# GPSDO_Controller.net
KiCad netlist of a schematic drawn in Altium Designer
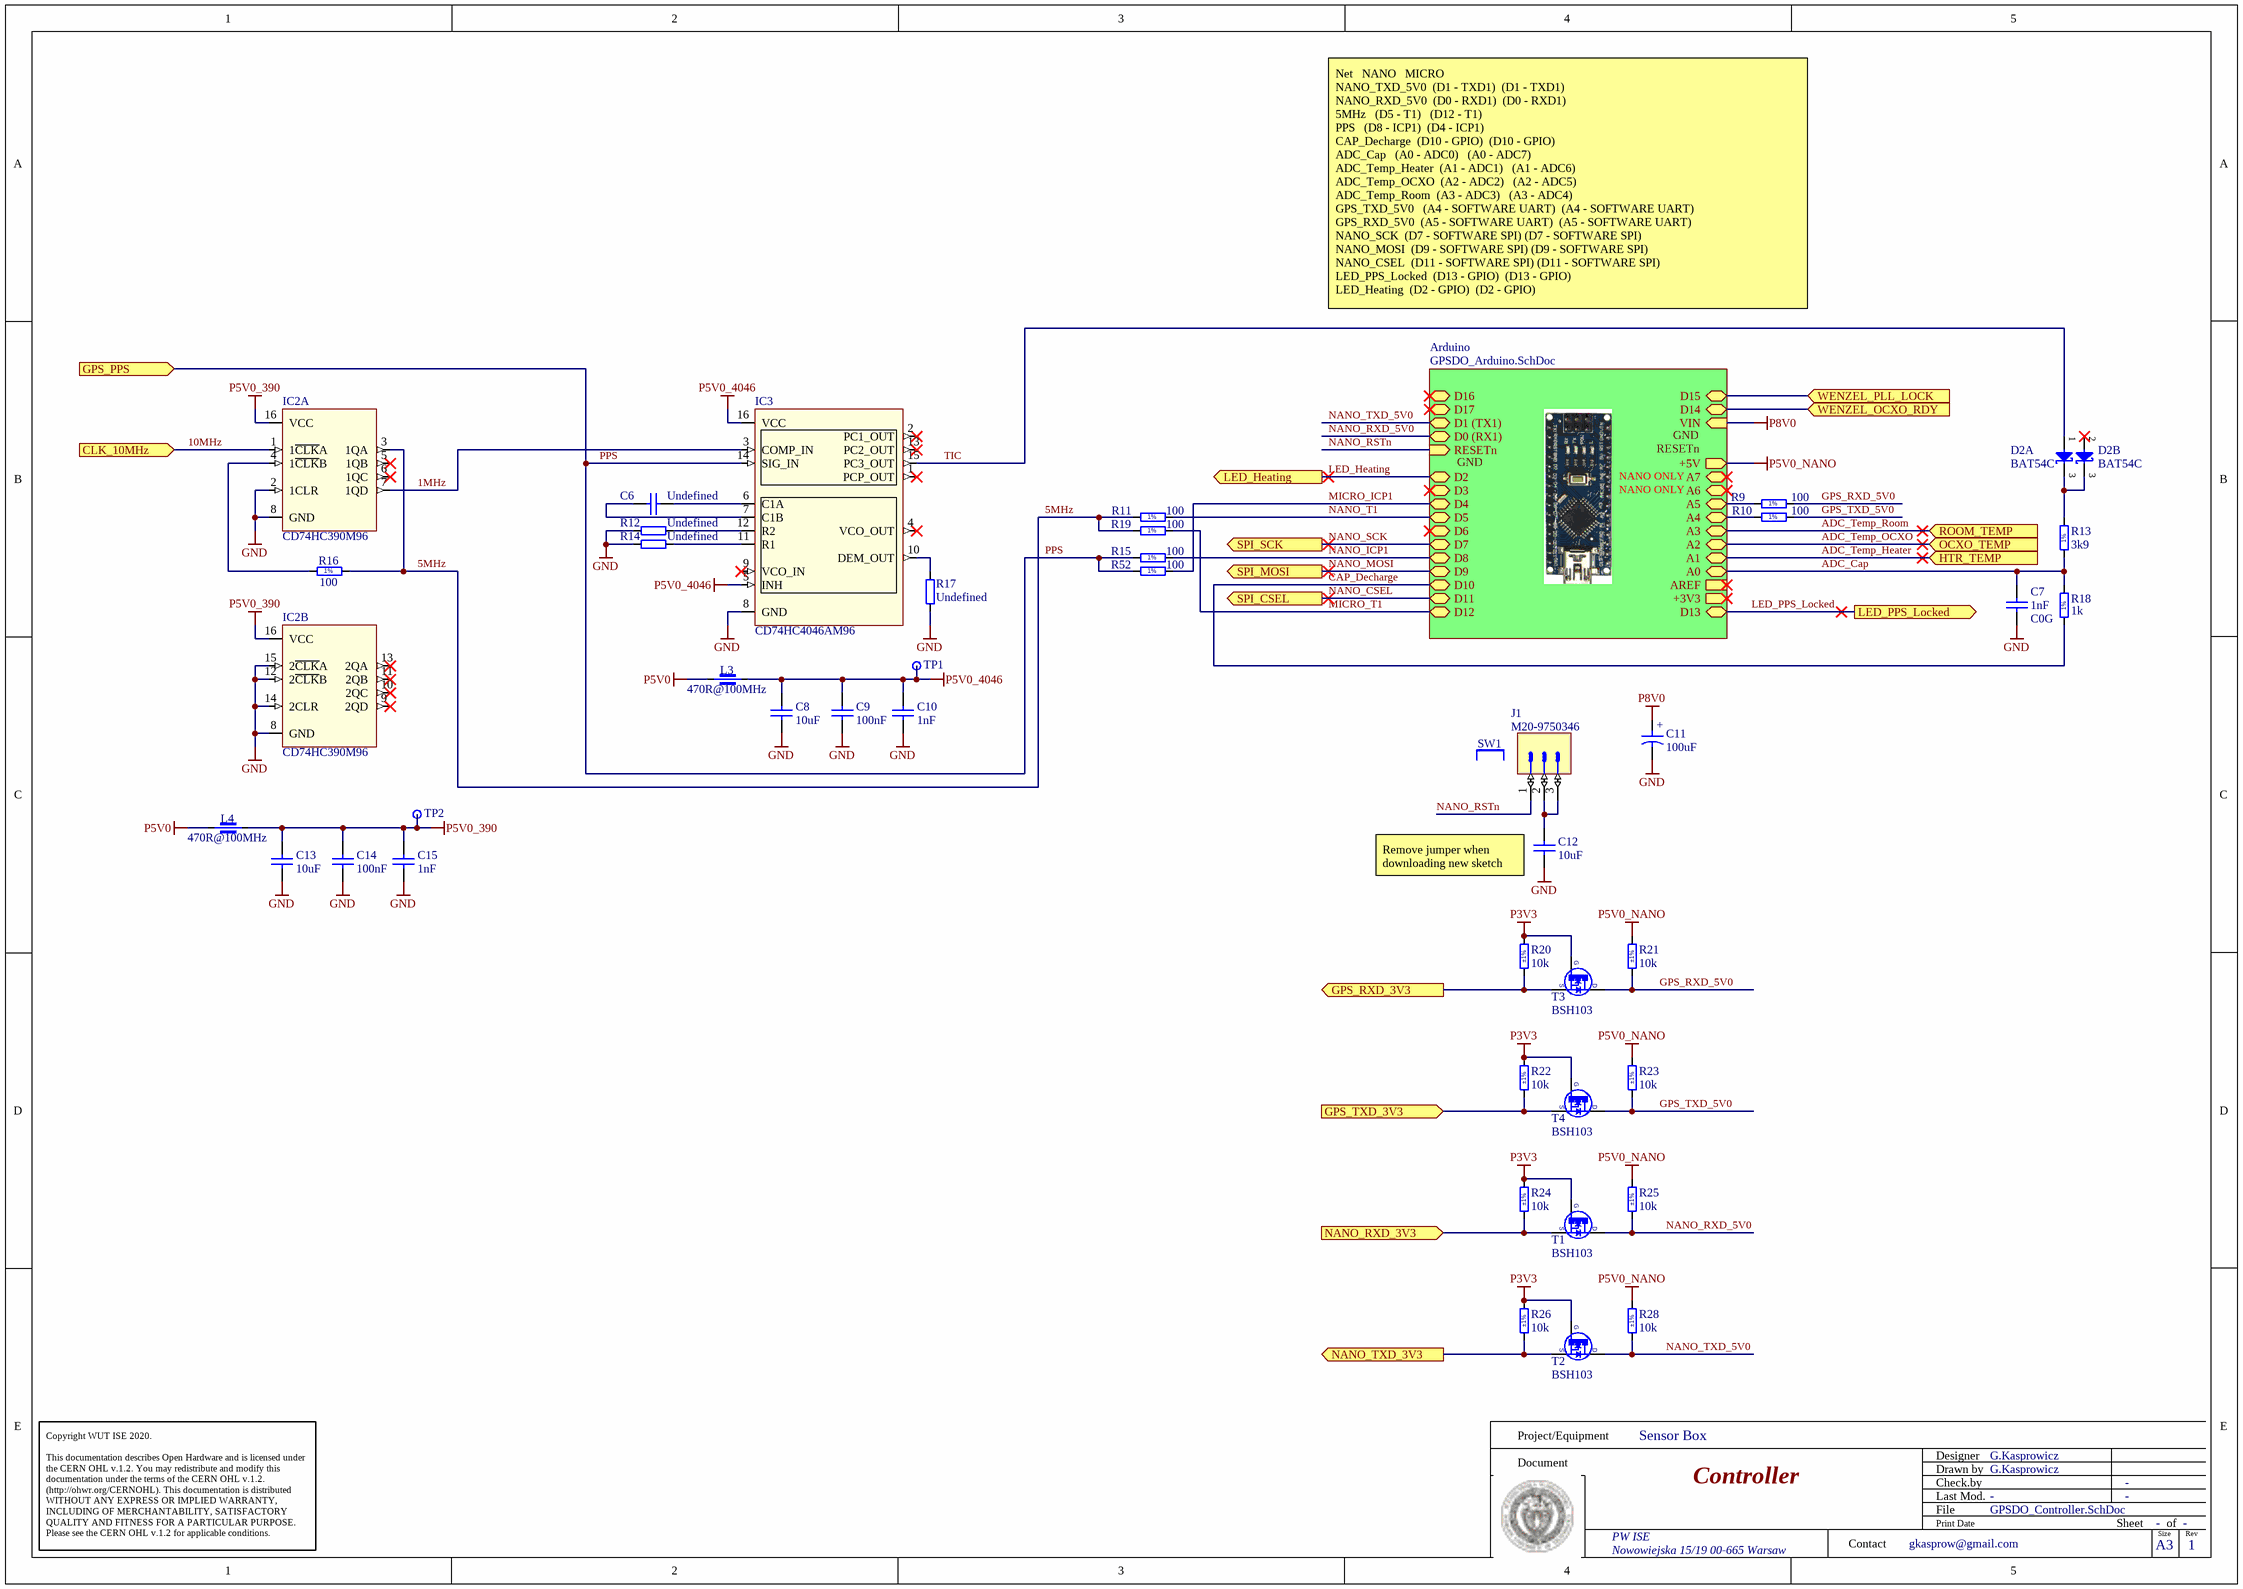
[diagram p0: GPSDO_Controller.SchDoc]

(export (version "E")
  (design (tool "Eeschema 10.0.6"))
  (components
    (comp (ref "C6")
      (value "Undefined")
      (footprint "CAPC1005X55N")
      (description "Non-polarised capacitor")
      (fields (field (name "PART NUMBER") "CC0402_NO-VALUE") (field (name "AUTHOR") "CERN DEM JLC"))
      (libsource (lib "Capacitors") (part "Capacitor - non polarized"))
    )
    (comp (ref "C7")
      (value "1nF")
      (footprint "CAPC1608X90N")
      (description "Non-polarised capacitor")
      (fields
        (field (name "PART NUMBER") "CC0603_1NF_50V_1%_NP0")
        (field (name "VOLTAGE") "50V")
        (field (name "TC") "C0G")
        (field (name "AUTHOR") "CERN DEM JLC")
      )
      (libsource (lib "Capacitors") (part "Capacitor - non polarized"))
    )
    (comp (ref "C8")
      (value "10uF")
      (footprint "CAPC1608X80N")
      (description "Non-polarised capacitor")
      (fields
        (field (name "PART NUMBER") "CC0603_10UF_10V_10%_X5R")
        (field (name "VOLTAGE") "10V")
        (field (name "AUTHOR") "CERN DEM JLC")
      )
      (libsource (lib "Capacitors") (part "Capacitor - non polarized"))
    )
    (comp (ref "C9")
      (value "100nF")
      (footprint "CAPC1005X55N")
      (description "Non-polarised capacitor")
      (fields
        (field (name "PART NUMBER") "CC0402_100NF_16V_10%_X5R")
        (field (name "VOLTAGE") "16V")
        (field (name "AUTHOR") "CERN DEM JLC")
      )
      (libsource (lib "Capacitors") (part "Capacitor - non polarized"))
    )
    (comp (ref "C10")
      (value "1nF")
      (footprint "CAPC1608X90N")
      (description "Non-polarised capacitor")
      (fields
        (field (name "PART NUMBER") "CC0603_1NF_50V_1%_NP0")
        (field (name "VOLTAGE") "50V")
        (field (name "AUTHOR") "CERN DEM JLC")
      )
      (libsource (lib "Capacitors") (part "Capacitor - non polarized"))
    )
    (comp (ref "C11")
      (value "100uF")
      (footprint "CAPMP7343X310N")
      (description "Polarised capacitor")
      (fields
        (field (name "PART NUMBER") "CTE7343-31_100UF_20V_10%")
        (field (name "VOLTAGE") "20V")
        (field (name "AUTHOR") "CERN DEM JLC")
      )
      (libsource (lib "Capacitors") (part "Capacitor - polarized"))
    )
    (comp (ref "C12")
      (value "10uF")
      (footprint "CAPC1608X80N")
      (description "Non-polarised capacitor")
      (fields
        (field (name "PART NUMBER") "CC0603_10UF_10V_10%_X5R")
        (field (name "VOLTAGE") "10V")
        (field (name "AUTHOR") "CERN DEM JLC")
      )
      (libsource (lib "Capacitors") (part "Capacitor - non polarized"))
    )
    (comp (ref "C13")
      (value "10uF")
      (footprint "CAPC1608X80N")
      (description "Non-polarised capacitor")
      (fields
        (field (name "PART NUMBER") "CC0603_10UF_10V_10%_X5R")
        (field (name "VOLTAGE") "10V")
        (field (name "AUTHOR") "CERN DEM JLC")
      )
      (libsource (lib "Capacitors") (part "Capacitor - non polarized"))
    )
    (comp (ref "C14")
      (value "100nF")
      (footprint "CAPC1005X55N")
      (description "Non-polarised capacitor")
      (fields
        (field (name "PART NUMBER") "CC0402_100NF_16V_10%_X5R")
        (field (name "VOLTAGE") "16V")
        (field (name "AUTHOR") "CERN DEM JLC")
      )
      (libsource (lib "Capacitors") (part "Capacitor - non polarized"))
    )
    (comp (ref "C15")
      (value "1nF")
      (footprint "CAPC1608X90N")
      (description "Non-polarised capacitor")
      (fields
        (field (name "PART NUMBER") "CC0603_1NF_50V_1%_NP0")
        (field (name "VOLTAGE") "50V")
        (field (name "AUTHOR") "CERN DEM JLC")
      )
      (libsource (lib "Capacitors") (part "Capacitor - non polarized"))
    )
    (comp (ref "D2")
      (value "BAT54C")
      (footprint "SOT95P240X130-3N")
      (description "Dual Common Cathode Schottky Diodes")
      (fields
        (field (name "VOLTAGE") "30V")
        (field (name "POWER") "200mA")
        (field (name "AUTHOR") "CERN DEM JLC")
      )
      (libsource (lib "ICs And Semiconductors") (part "Diode Schottky x2 A1C3_A2C3"))
    )
    (comp (ref "IC2")
      (value "CD74HC390M96")
      (footprint "SOIC127P600X175-16N")
      (libsource (lib "Lib") (part "74HC390"))
    )
    (comp (ref "IC3")
      (value "CD74HC4046AM96")
      (footprint "SOIC127P600X175-16N")
      (libsource (lib "Lib") (part "74HC4046A"))
    )
    (comp (ref "J1")
      (value "M20-9750346")
      (footprint "HARWIN_M20-9750346")
      (description "Connector 3 Male 2.54mm")
      (fields (field (name "MANUFACTURER") "Harwin"))
      (libsource (lib "Connectors") (part "Connector 3 Male_1"))
    )
    (comp (ref "L3")
      (value "470R@100MHz")
      (footprint "INDC1608X95N")
      (fields
        (field (name "PART NUMBER") "IND0603_MURATA_BLM18PG471SN1D")
        (field (name "POWER") "1A")
        (field (name "TOLERANCE") "±25%")
        (field (name "AUTHOR") "CERN DEM BC")
      )
      (libsource (lib "Inductors & Transformers") (part "Ferrite Bead"))
    )
    (comp (ref "L4")
      (value "470R@100MHz")
      (footprint "INDC1608X95N")
      (fields
        (field (name "PART NUMBER") "IND0603_MURATA_BLM18PG471SN1D")
        (field (name "POWER") "1A")
        (field (name "TOLERANCE") "±25%")
        (field (name "AUTHOR") "CERN DEM BC")
      )
      (libsource (lib "Inductors & Transformers") (part "Ferrite Bead"))
    )
    (comp (ref "R9")
      (value "100")
      (footprint "RESC1005X40N")
      (description "Resistor - 1%")
      (fields
        (field (name "PART NUMBER") "R0402_100R_1%_0.0625W_100PPM")
        (field (name "POWER") "0.0625W")
        (field (name "AUTHOR") "CERN DEM JLC")
      )
      (libsource (lib "Resistors") (part "Resistor - 1%"))
    )
    (comp (ref "R10")
      (value "100")
      (footprint "RESC1005X40N")
      (description "Resistor - 1%")
      (fields
        (field (name "PART NUMBER") "R0402_100R_1%_0.0625W_100PPM")
        (field (name "POWER") "0.0625W")
        (field (name "AUTHOR") "CERN DEM JLC")
      )
      (libsource (lib "Resistors") (part "Resistor - 1%"))
    )
    (comp (ref "R11")
      (value "100")
      (footprint "RESC1005X40N")
      (description "Resistor - 1%")
      (fields
        (field (name "PART NUMBER") "R0402_100R_1%_0.0625W_100PPM")
        (field (name "POWER") "0.0625W")
        (field (name "AUTHOR") "CERN DEM JLC")
      )
      (libsource (lib "Resistors") (part "Resistor - 1%"))
    )
    (comp (ref "R12")
      (value "Undefined")
      (footprint "RESC1005X40N")
      (description "Resistor")
      (fields (field (name "PART NUMBER") "R0402_NO-VALUE") (field (name "AUTHOR") "CERN DEM JLC"))
      (libsource (lib "Resistors") (part "Resistor"))
    )
    (comp (ref "R13")
      (value "3k9")
      (footprint "RESC1005X40N")
      (description "Resistor - 1%")
      (fields
        (field (name "PART NUMBER") "R0402_3K9_1%_0.0625W_100PPM")
        (field (name "POWER") "0.0625W")
        (field (name "AUTHOR") "CERN DEM JLC")
      )
      (libsource (lib "Resistors") (part "Resistor - 1%"))
    )
    (comp (ref "R14")
      (value "Undefined")
      (footprint "RESC1005X40N")
      (description "Resistor")
      (fields (field (name "PART NUMBER") "R0402_NO-VALUE") (field (name "AUTHOR") "CERN DEM JLC"))
      (libsource (lib "Resistors") (part "Resistor"))
    )
    (comp (ref "R15")
      (value "100")
      (footprint "RESC1005X40N")
      (description "Resistor - 1%")
      (fields
        (field (name "PART NUMBER") "R0402_100R_1%_0.0625W_100PPM")
        (field (name "POWER") "0.0625W")
        (field (name "AUTHOR") "CERN DEM JLC")
      )
      (libsource (lib "Resistors") (part "Resistor - 1%"))
    )
    (comp (ref "R16")
      (value "100")
      (footprint "RESC1005X40N")
      (description "Resistor - 1%")
      (fields
        (field (name "PART NUMBER") "R0402_100R_1%_0.0625W_100PPM")
        (field (name "POWER") "0.0625W")
        (field (name "AUTHOR") "CERN DEM JLC")
      )
      (libsource (lib "Resistors") (part "Resistor - 1%"))
    )
    (comp (ref "R17")
      (value "Undefined")
      (footprint "RESC1005X40N")
      (description "Resistor")
      (fields (field (name "PART NUMBER") "R0402_NO-VALUE") (field (name "AUTHOR") "CERN DEM JLC"))
      (libsource (lib "Resistors") (part "Resistor"))
    )
    (comp (ref "R18")
      (value "1k")
      (footprint "RESC1005X40N")
      (description "Resistor - 1%")
      (fields
        (field (name "PART NUMBER") "R0402_1K_1%_0.0625W_100PPM")
        (field (name "POWER") "0.0625W")
        (field (name "AUTHOR") "CERN DEM JLC")
      )
      (libsource (lib "Resistors") (part "Resistor - 1%"))
    )
    (comp (ref "R19")
      (value "100")
      (footprint "RESC1005X40N")
      (description "Resistor - 1%")
      (fields
        (field (name "PART NUMBER") "R0402_100R_1%_0.0625W_100PPM")
        (field (name "POWER") "0.0625W")
        (field (name "AUTHOR") "CERN DEM JLC")
      )
      (libsource (lib "Resistors") (part "Resistor - 1%"))
    )
    (comp (ref "R20")
      (value "10k")
      (footprint "RESC1005X40N")
      (description "Resistor - 1%")
      (fields
        (field (name "TOLERANCE") "±1%")
        (field (name "PART NUMBER") "R0402_10K_1%_0.0625W_100PPM")
        (field (name "POWER") "0.0625W")
        (field (name "AUTHOR") "CERN DEM JLC")
      )
      (libsource (lib "Resistors") (part "Resistor - 1%"))
    )
    (comp (ref "R21")
      (value "10k")
      (footprint "RESC1005X40N")
      (description "Resistor - 1%")
      (fields
        (field (name "TOLERANCE") "±1%")
        (field (name "PART NUMBER") "R0402_10K_1%_0.0625W_100PPM")
        (field (name "POWER") "0.0625W")
        (field (name "AUTHOR") "CERN DEM JLC")
      )
      (libsource (lib "Resistors") (part "Resistor - 1%"))
    )
    (comp (ref "R22")
      (value "10k")
      (footprint "RESC1005X40N")
      (description "Resistor - 1%")
      (fields
        (field (name "TOLERANCE") "±1%")
        (field (name "PART NUMBER") "R0402_10K_1%_0.0625W_100PPM")
        (field (name "POWER") "0.0625W")
        (field (name "AUTHOR") "CERN DEM JLC")
      )
      (libsource (lib "Resistors") (part "Resistor - 1%"))
    )
    (comp (ref "R23")
      (value "10k")
      (footprint "RESC1005X40N")
      (description "Resistor - 1%")
      (fields
        (field (name "TOLERANCE") "±1%")
        (field (name "PART NUMBER") "R0402_10K_1%_0.0625W_100PPM")
        (field (name "POWER") "0.0625W")
        (field (name "AUTHOR") "CERN DEM JLC")
      )
      (libsource (lib "Resistors") (part "Resistor - 1%"))
    )
    (comp (ref "R24")
      (value "10k")
      (footprint "RESC1005X40N")
      (description "Resistor - 1%")
      (fields
        (field (name "TOLERANCE") "±1%")
        (field (name "PART NUMBER") "R0402_10K_1%_0.0625W_100PPM")
        (field (name "POWER") "0.0625W")
        (field (name "AUTHOR") "CERN DEM JLC")
      )
      (libsource (lib "Resistors") (part "Resistor - 1%"))
    )
    (comp (ref "R25")
      (value "10k")
      (footprint "RESC1005X40N")
      (description "Resistor - 1%")
      (fields
        (field (name "TOLERANCE") "±1%")
        (field (name "PART NUMBER") "R0402_10K_1%_0.0625W_100PPM")
        (field (name "POWER") "0.0625W")
        (field (name "AUTHOR") "CERN DEM JLC")
      )
      (libsource (lib "Resistors") (part "Resistor - 1%"))
    )
    (comp (ref "R26")
      (value "10k")
      (footprint "RESC1005X40N")
      (description "Resistor - 1%")
      (fields
        (field (name "TOLERANCE") "±1%")
        (field (name "PART NUMBER") "R0402_10K_1%_0.0625W_100PPM")
        (field (name "POWER") "0.0625W")
        (field (name "AUTHOR") "CERN DEM JLC")
      )
      (libsource (lib "Resistors") (part "Resistor - 1%"))
    )
    (comp (ref "R28")
      (value "10k")
      (footprint "RESC1005X40N")
      (description "Resistor - 1%")
      (fields
        (field (name "TOLERANCE") "±1%")
        (field (name "PART NUMBER") "R0402_10K_1%_0.0625W_100PPM")
        (field (name "POWER") "0.0625W")
        (field (name "AUTHOR") "CERN DEM JLC")
      )
      (libsource (lib "Resistors") (part "Resistor - 1%"))
    )
    (comp (ref "R52")
      (value "100")
      (footprint "RESC1005X40N")
      (description "Resistor - 1%")
      (fields
        (field (name "PART NUMBER") "R0402_100R_1%_0.0625W_100PPM")
        (field (name "POWER") "0.0625W")
        (field (name "AUTHOR") "CERN DEM JLC")
      )
      (libsource (lib "Resistors") (part "Resistor - 1%"))
    )
    (comp (ref "SW1")
      (value "M7582-46")
      (footprint "HARWIN_M7582-46")
      (description "Jumper 1 Pin")
      (fields (field (name "MANUFACTURER") "Harwin"))
      (libsource (lib "Connectors") (part "HARWIN_M7582-46"))
    )
    (comp (ref "T1")
      (value "BSH103")
      (footprint "SOT95P230X110-3N")
      (description "N-CHANNEL MOSFET WITH DIODE")
      (fields (field (name "MANUFACTURER") "NEXPERIA") (field (name "AUTHOR") "CERN DEM JLC"))
      (libsource (lib "ICs And Semiconductors") (part "N-MOSFET-D 1G 2S 3D"))
    )
    (comp (ref "T2")
      (value "BSH103")
      (footprint "SOT95P230X110-3N")
      (description "N-CHANNEL MOSFET WITH DIODE")
      (fields (field (name "MANUFACTURER") "NEXPERIA") (field (name "AUTHOR") "CERN DEM JLC"))
      (libsource (lib "ICs And Semiconductors") (part "N-MOSFET-D 1G 2S 3D"))
    )
    (comp (ref "T3")
      (value "BSH103")
      (footprint "SOT95P230X110-3N")
      (description "N-CHANNEL MOSFET WITH DIODE")
      (fields (field (name "MANUFACTURER") "NEXPERIA") (field (name "AUTHOR") "CERN DEM JLC"))
      (libsource (lib "ICs And Semiconductors") (part "N-MOSFET-D 1G 2S 3D"))
    )
    (comp (ref "T4")
      (value "BSH103")
      (footprint "SOT95P230X110-3N")
      (description "N-CHANNEL MOSFET WITH DIODE")
      (fields (field (name "MANUFACTURER") "NEXPERIA") (field (name "AUTHOR") "CERN DEM JLC"))
      (libsource (lib "ICs And Semiconductors") (part "N-MOSFET-D 1G 2S 3D"))
    )
    (comp (ref "TP1")
      (value "Test Point")
      (footprint "TPS127")
      (fields (field (name "PART NUMBER") "SMD_PAD_1.27X1.27MM") (field (name "AUTHOR") "CERN DEM JLC"))
      (libsource (lib "Eletro-mechanical") (part "Test Point"))
    )
    (comp (ref "TP2")
      (value "Test Point")
      (footprint "TPS127")
      (fields (field (name "PART NUMBER") "SMD_PAD_1.27X1.27MM") (field (name "AUTHOR") "CERN DEM JLC"))
      (libsource (lib "Eletro-mechanical") (part "Test Point"))
    )
  )
  (nets
    (net (code "2") (name "/1MHz") (class "Default")
      (node (ref "IC2") (pin "7") (pinfunction "1QD_7") (pintype "output"))
      (node (ref "IC3") (pin "3") (pinfunction "COMP_IN_3") (pintype "input"))
    )
    (net (code "3") (name "/5MHz") (class "Default")
      (node (ref "IC2") (pin "3") (pinfunction "1QA_3") (pintype "output"))
      (node (ref "R11") (pin "1") (pinfunction "1_1") (pintype "passive"))
      (node (ref "R16") (pin "2") (pinfunction "2_2") (pintype "passive"))
      (node (ref "R19") (pin "1") (pinfunction "1_1") (pintype "passive"))
    )
    (net (code "4") (name "/10MHz") (class "Default")
      (node (ref "IC2") (pin "1") (pinfunction "1~{CLK}A_1") (pintype "input"))
    )
    (net (code "5") (name "/A4") (class "Default")
      (node (ref "R10") (pin "1") (pinfunction "1_1") (pintype "passive"))
    )
    (net (code "6") (name "/A5") (class "Default")
      (node (ref "R9") (pin "1") (pinfunction "1_1") (pintype "passive"))
    )
    (net (code "9") (name "/ADC_Cap") (class "Default")
      (node (ref "C7") (pin "2") (pinfunction "2_2") (pintype "passive"))
      (node (ref "R13") (pin "1") (pinfunction "1_1") (pintype "passive"))
      (node (ref "R18") (pin "2") (pinfunction "2_2") (pintype "passive"))
    )
    (net (code "14") (name "/CAP_Decharge") (class "Default")
      (node (ref "R18") (pin "1") (pinfunction "1_1") (pintype "passive"))
    )
    (net (code "19") (name "/GPS_RXD_3V3") (class "Default")
      (node (ref "R20") (pin "1") (pinfunction "1_1") (pintype "passive"))
      (node (ref "T3") (pin "2") (pinfunction "S_2") (pintype "passive"))
    )
    (net (code "20") (name "/GPS_RXD_5V0") (class "Default")
      (node (ref "R21") (pin "1") (pinfunction "1_1") (pintype "passive"))
      (node (ref "R9") (pin "2") (pinfunction "2_2") (pintype "passive"))
      (node (ref "T3") (pin "3") (pinfunction "D_3") (pintype "passive"))
    )
    (net (code "21") (name "/GPS_TXD_3V3") (class "Default")
      (node (ref "R22") (pin "1") (pinfunction "1_1") (pintype "passive"))
      (node (ref "T4") (pin "2") (pinfunction "S_2") (pintype "passive"))
    )
    (net (code "22") (name "/GPS_TXD_5V0") (class "Default")
      (node (ref "R10") (pin "2") (pinfunction "2_2") (pintype "passive"))
      (node (ref "R23") (pin "1") (pinfunction "1_1") (pintype "passive"))
      (node (ref "T4") (pin "3") (pinfunction "D_3") (pintype "passive"))
    )
    (net (code "25") (name "/MICRO_ICP1") (class "Default")
      (node (ref "R52") (pin "2") (pinfunction "2_2") (pintype "passive"))
    )
    (net (code "26") (name "/MICRO_T1") (class "Default")
      (node (ref "R19") (pin "2") (pinfunction "2_2") (pintype "passive"))
    )
    (net (code "28") (name "/NANO_ICP1") (class "Default")
      (node (ref "R15") (pin "2") (pinfunction "2_2") (pintype "passive"))
    )
    (net (code "30") (name "/NANO_RSTn") (class "Default")
      (node (ref "J1") (pin "1") (pinfunction "1_1") (pintype "bidirectional"))
    )
    (net (code "31") (name "/NANO_RXD_3V3") (class "Default")
      (node (ref "R24") (pin "1") (pinfunction "1_1") (pintype "passive"))
      (node (ref "T1") (pin "2") (pinfunction "S_2") (pintype "passive"))
    )
    (net (code "32") (name "/NANO_RXD_5V0") (class "Default")
      (node (ref "R25") (pin "1") (pinfunction "1_1") (pintype "passive"))
      (node (ref "T1") (pin "3") (pinfunction "D_3") (pintype "passive"))
    )
    (net (code "34") (name "/NANO_T1") (class "Default")
      (node (ref "R11") (pin "2") (pinfunction "2_2") (pintype "passive"))
    )
    (net (code "35") (name "/NANO_TXD_3V3") (class "Default")
      (node (ref "R26") (pin "1") (pinfunction "1_1") (pintype "passive"))
      (node (ref "T2") (pin "2") (pinfunction "S_2") (pintype "passive"))
    )
    (net (code "36") (name "/NANO_TXD_5V0") (class "Default")
      (node (ref "R28") (pin "1") (pinfunction "1_1") (pintype "passive"))
      (node (ref "T2") (pin "3") (pinfunction "D_3") (pintype "passive"))
    )
    (net (code "37") (name "/PPS") (class "Default")
      (node (ref "IC3") (pin "14") (pinfunction "SIG_IN_14") (pintype "input"))
      (node (ref "R15") (pin "1") (pinfunction "1_1") (pintype "passive"))
      (node (ref "R52") (pin "1") (pinfunction "1_1") (pintype "passive"))
    )
    (net (code "41") (name "/TIC") (class "Default")
      (node (ref "D2") (pin "1") (pinfunction "A_1") (pintype "passive"))
      (node (ref "IC3") (pin "15") (pinfunction "PC3_OUT_15") (pintype "output"))
    )
    (net (code "44") (name "GND") (class "Default")
      (node (ref "C10") (pin "1") (pinfunction "1_1") (pintype "passive"))
      (node (ref "C11") (pin "2") (pinfunction "2_2") (pintype "passive"))
      (node (ref "C12") (pin "1") (pinfunction "1_1") (pintype "passive"))
      (node (ref "C13") (pin "1") (pinfunction "1_1") (pintype "passive"))
      (node (ref "C14") (pin "1") (pinfunction "1_1") (pintype "passive"))
      (node (ref "C15") (pin "1") (pinfunction "1_1") (pintype "passive"))
      (node (ref "C7") (pin "1") (pinfunction "1_1") (pintype "passive"))
      (node (ref "C8") (pin "1") (pinfunction "1_1") (pintype "passive"))
      (node (ref "C9") (pin "1") (pinfunction "1_1") (pintype "passive"))
      (node (ref "IC2") (pin "12") (pinfunction "2~{CLK}B_12") (pintype "input"))
      (node (ref "IC2") (pin "14") (pinfunction "2CLR_14") (pintype "input"))
      (node (ref "IC2") (pin "15") (pinfunction "2~{CLK}A_15") (pintype "input"))
      (node (ref "IC2") (pin "2") (pinfunction "1CLR_2") (pintype "input"))
      (node (ref "IC2") (pin "8") (pinfunction "GND_8") (pintype "passive"))
      (node (ref "IC3") (pin "8") (pinfunction "GND_8") (pintype "passive"))
      (node (ref "R12") (pin "1") (pinfunction "1_1") (pintype "passive"))
      (node (ref "R14") (pin "1") (pinfunction "1_1") (pintype "passive"))
      (node (ref "R17") (pin "1") (pinfunction "1_1") (pintype "passive"))
    )
    (net (code "45") (name "Net-(C12-Pad2)") (class "Default")
      (node (ref "C12") (pin "2") (pinfunction "2_2") (pintype "passive"))
      (node (ref "J1") (pin "2") (pinfunction "2_2") (pintype "bidirectional"))
      (node (ref "J1") (pin "3") (pinfunction "3_3") (pintype "bidirectional"))
    )
    (net (code "46") (name "Net-(D2A-COMC)") (class "Default")
      (node (ref "D2") (pin "3") (pinfunction "COMC_3") (pintype "passive"))
      (node (ref "R13") (pin "2") (pinfunction "2_2") (pintype "passive"))
    )
    (net (code "47") (name "Net-(IC2A-1~{CLK}B)") (class "Default")
      (node (ref "IC2") (pin "4") (pinfunction "1~{CLK}B_4") (pintype "input"))
      (node (ref "R16") (pin "1") (pinfunction "1_1") (pintype "passive"))
    )
    (net (code "48") (name "Net-(IC3-C1A)") (class "Default")
      (node (ref "C6") (pin "2") (pinfunction "2_2") (pintype "passive"))
      (node (ref "IC3") (pin "6") (pinfunction "C1A_6") (pintype "passive"))
    )
    (net (code "49") (name "Net-(IC3-C1B)") (class "Default")
      (node (ref "C6") (pin "1") (pinfunction "1_1") (pintype "passive"))
      (node (ref "IC3") (pin "7") (pinfunction "C1B_7") (pintype "passive"))
    )
    (net (code "50") (name "Net-(IC3-DEM_OUT)") (class "Default")
      (node (ref "IC3") (pin "10") (pinfunction "DEM_OUT_10") (pintype "output"))
      (node (ref "R17") (pin "2") (pinfunction "2_2") (pintype "passive"))
    )
    (net (code "51") (name "Net-(IC3-R1)") (class "Default")
      (node (ref "IC3") (pin "11") (pinfunction "R1_11") (pintype "passive"))
      (node (ref "R14") (pin "2") (pinfunction "2_2") (pintype "passive"))
    )
    (net (code "52") (name "Net-(IC3-R2)") (class "Default")
      (node (ref "IC3") (pin "12") (pinfunction "R2_12") (pintype "passive"))
      (node (ref "R12") (pin "2") (pinfunction "2_2") (pintype "passive"))
    )
    (net (code "53") (name "P3V3") (class "Default")
      (node (ref "R20") (pin "2") (pinfunction "2_2") (pintype "passive"))
      (node (ref "R22") (pin "2") (pinfunction "2_2") (pintype "passive"))
      (node (ref "R24") (pin "2") (pinfunction "2_2") (pintype "passive"))
      (node (ref "R26") (pin "2") (pinfunction "2_2") (pintype "passive"))
      (node (ref "T1") (pin "1") (pinfunction "G_1") (pintype "passive"))
      (node (ref "T2") (pin "1") (pinfunction "G_1") (pintype "passive"))
      (node (ref "T3") (pin "1") (pinfunction "G_1") (pintype "passive"))
      (node (ref "T4") (pin "1") (pinfunction "G_1") (pintype "passive"))
    )
    (net (code "54") (name "P5V0") (class "Default")
      (node (ref "L3") (pin "1") (pinfunction "1_1") (pintype "passive"))
      (node (ref "L4") (pin "1") (pinfunction "1_1") (pintype "passive"))
    )
    (net (code "55") (name "P5V0_390") (class "Default")
      (node (ref "C13") (pin "2") (pinfunction "2_2") (pintype "passive"))
      (node (ref "C14") (pin "2") (pinfunction "2_2") (pintype "passive"))
      (node (ref "C15") (pin "2") (pinfunction "2_2") (pintype "passive"))
      (node (ref "IC2") (pin "16") (pinfunction "VCC_16") (pintype "passive"))
      (node (ref "L4") (pin "2") (pinfunction "2_2") (pintype "passive"))
      (node (ref "TP2") (pin "1") (pinfunction "1_1") (pintype "bidirectional"))
    )
    (net (code "56") (name "P5V0_4046") (class "Default")
      (node (ref "C10") (pin "2") (pinfunction "2_2") (pintype "passive"))
      (node (ref "C8") (pin "2") (pinfunction "2_2") (pintype "passive"))
      (node (ref "C9") (pin "2") (pinfunction "2_2") (pintype "passive"))
      (node (ref "IC3") (pin "16") (pinfunction "VCC_16") (pintype "passive"))
      (node (ref "IC3") (pin "5") (pinfunction "INH_5") (pintype "input"))
      (node (ref "L3") (pin "2") (pinfunction "2_2") (pintype "passive"))
      (node (ref "TP1") (pin "1") (pinfunction "1_1") (pintype "bidirectional"))
    )
    (net (code "57") (name "P5V0_NANO") (class "Default")
      (node (ref "R21") (pin "2") (pinfunction "2_2") (pintype "passive"))
      (node (ref "R23") (pin "2") (pinfunction "2_2") (pintype "passive"))
      (node (ref "R25") (pin "2") (pinfunction "2_2") (pintype "passive"))
      (node (ref "R28") (pin "2") (pinfunction "2_2") (pintype "passive"))
    )
    (net (code "58") (name "P8V0") (class "Default")
      (node (ref "C11") (pin "1") (pinfunction "1_1") (pintype "passive"))
    )
    (net (code "59") (name "unconnected-(D2B-A-Pad2)") (class "Default")
      (node (ref "D2") (pin "2") (pinfunction "A_2") (pintype "passive+no_connect"))
    )
    (net (code "60") (name "unconnected-(IC2A-1QB-Pad5)") (class "Default")
      (node (ref "IC2") (pin "5") (pinfunction "1QB_5") (pintype "output+no_connect"))
    )
    (net (code "61") (name "unconnected-(IC2A-1QC-Pad6)") (class "Default")
      (node (ref "IC2") (pin "6") (pinfunction "1QC_6") (pintype "output+no_connect"))
    )
    (net (code "62") (name "unconnected-(IC2B-2QA-Pad13)") (class "Default")
      (node (ref "IC2") (pin "13") (pinfunction "2QA_13") (pintype "output+no_connect"))
    )
    (net (code "63") (name "unconnected-(IC2B-2QB-Pad11)") (class "Default")
      (node (ref "IC2") (pin "11") (pinfunction "2QB_11") (pintype "output+no_connect"))
    )
    (net (code "64") (name "unconnected-(IC2B-2QC-Pad10)") (class "Default")
      (node (ref "IC2") (pin "10") (pinfunction "2QC_10") (pintype "output+no_connect"))
    )
    (net (code "65") (name "unconnected-(IC2B-2QD-Pad9)") (class "Default")
      (node (ref "IC2") (pin "9") (pinfunction "2QD_9") (pintype "output+no_connect"))
    )
    (net (code "66") (name "unconnected-(IC3-PC1_OUT-Pad2)") (class "Default")
      (node (ref "IC3") (pin "2") (pinfunction "PC1_OUT_2") (pintype "output+no_connect"))
    )
    (net (code "67") (name "unconnected-(IC3-PC2_OUT-Pad13)") (class "Default")
      (node (ref "IC3") (pin "13") (pinfunction "PC2_OUT_13") (pintype "output+no_connect"))
    )
    (net (code "68") (name "unconnected-(IC3-PCP_OUT-Pad1)") (class "Default")
      (node (ref "IC3") (pin "1") (pinfunction "PCP_OUT_1") (pintype "output+no_connect"))
    )
    (net (code "69") (name "unconnected-(IC3-VCO_IN-Pad9)") (class "Default")
      (node (ref "IC3") (pin "9") (pinfunction "VCO_IN_9") (pintype "input+no_connect"))
    )
    (net (code "70") (name "unconnected-(IC3-VCO_OUT-Pad4)") (class "Default")
      (node (ref "IC3") (pin "4") (pinfunction "VCO_OUT_4") (pintype "output+no_connect"))
    )
    (net (code "71") (name "unconnected-(SW1-Pad1)") (class "Default")
      (node (ref "SW1") (pin "1") (pinfunction "1_1") (pintype "bidirectional"))
    )
  )
)
